# XRP_Controller.net
KiCad netlist of a schematic drawn in EAGLE
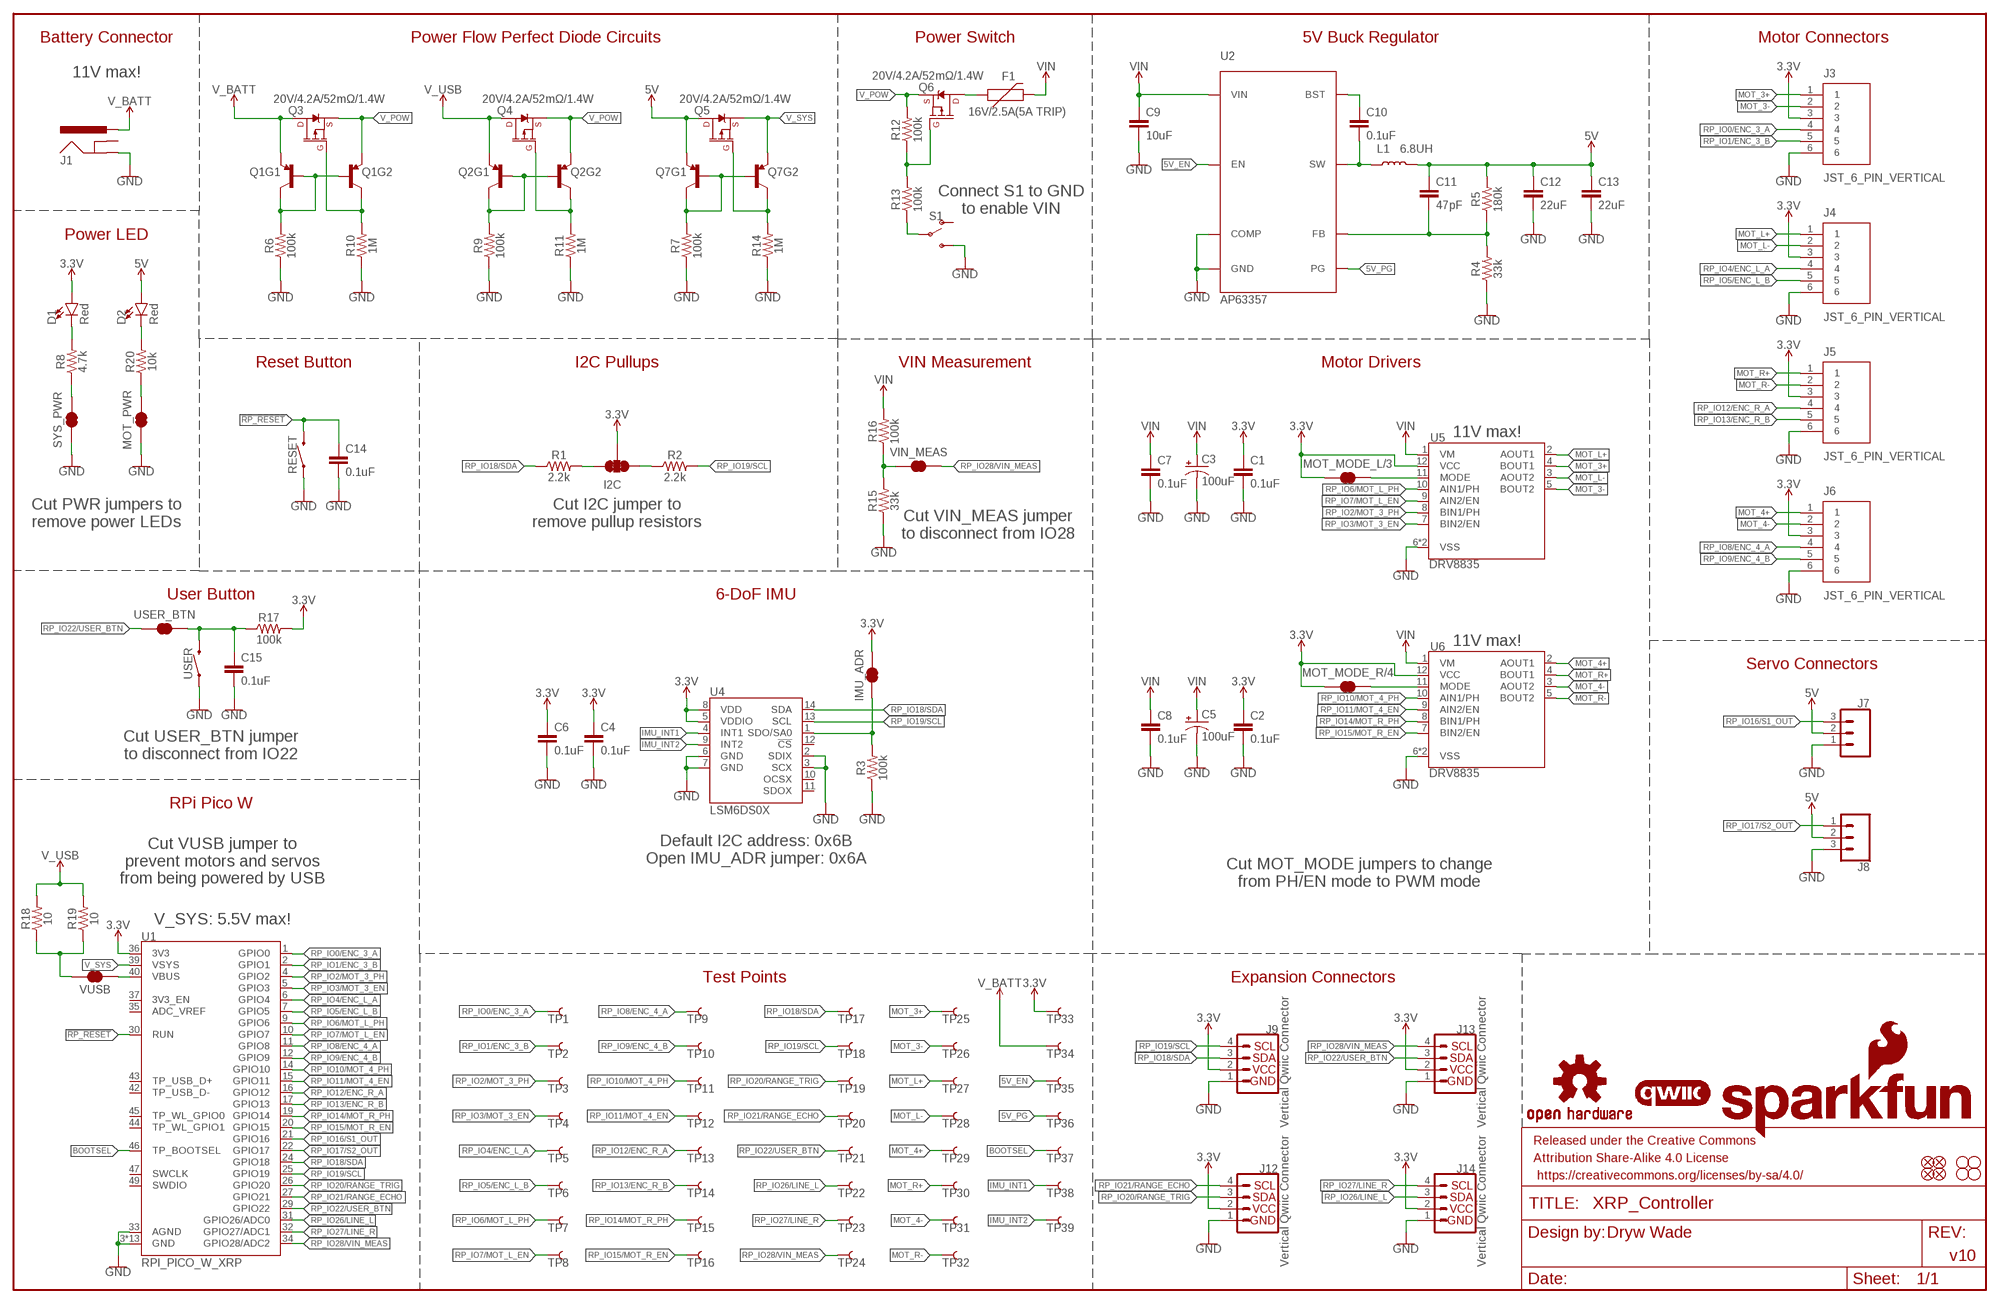
[diagram p0: schematic, sheet 1]

(export (version "E")
  (design (tool "Eeschema 10.0.6"))
  (components
    (comp (ref "C1")
      (value "0.1uF")
      (footprint "eagle-import:0603")
      (libsource (lib "eagle-import") (part "0.1UF-0603-25V-(+80/-20%)"))
    )
    (comp (ref "C2")
      (value "0.1uF")
      (footprint "eagle-import:0603")
      (libsource (lib "eagle-import") (part "0.1UF-0603-25V-(+80/-20%)"))
    )
    (comp (ref "C3")
      (value "100uF")
      (footprint "eagle-import:PANASONIC_D")
      (libsource (lib "eagle-import") (part "100UF-POLAR-25V-20%-SMD(ELEC)"))
    )
    (comp (ref "C4")
      (value "0.1uF")
      (footprint "eagle-import:0603")
      (libsource (lib "eagle-import") (part "0.1UF-0603-25V-(+80/-20%)"))
    )
    (comp (ref "C5")
      (value "100uF")
      (footprint "eagle-import:PANASONIC_D")
      (libsource (lib "eagle-import") (part "100UF-POLAR-25V-20%-SMD(ELEC)"))
    )
    (comp (ref "C6")
      (value "0.1uF")
      (footprint "eagle-import:0603")
      (libsource (lib "eagle-import") (part "0.1UF-0603-25V-(+80/-20%)"))
    )
    (comp (ref "C7")
      (value "0.1uF")
      (footprint "eagle-import:0603")
      (libsource (lib "eagle-import") (part "0.1UF-0603-25V-(+80/-20%)"))
    )
    (comp (ref "C8")
      (value "0.1uF")
      (footprint "eagle-import:0603")
      (libsource (lib "eagle-import") (part "0.1UF-0603-25V-(+80/-20%)"))
    )
    (comp (ref "C9")
      (value "10uF")
      (footprint "eagle-import:0805")
      (libsource (lib "eagle-import") (part "10UF-0805-25V-10%"))
    )
    (comp (ref "C10")
      (value "0.1uF")
      (footprint "eagle-import:0603")
      (libsource (lib "eagle-import") (part "0.1UF-0603-25V-(+80/-20%)"))
    )
    (comp (ref "C11")
      (value "47pF")
      (footprint "eagle-import:0603")
      (libsource (lib "eagle-import") (part "47PF-0603-50V-5%"))
    )
    (comp (ref "C12")
      (value "22uF")
      (footprint "eagle-import:0805")
      (libsource (lib "eagle-import") (part "22UF-0805-16V-20%"))
    )
    (comp (ref "C13")
      (value "22uF")
      (footprint "eagle-import:0805")
      (libsource (lib "eagle-import") (part "22UF-0805-16V-20%"))
    )
    (comp (ref "C14")
      (value "0.1uF")
      (footprint "eagle-import:0603")
      (libsource (lib "eagle-import") (part "0.1UF-0603-25V-(+80/-20%)"))
    )
    (comp (ref "C15")
      (value "0.1uF")
      (footprint "eagle-import:0603")
      (libsource (lib "eagle-import") (part "0.1UF-0603-25V-(+80/-20%)"))
    )
    (comp (ref "D1")
      (value "Red")
      (footprint "eagle-import:LED-0603")
      (libsource (lib "eagle-import") (part "LED-RED_0603-KB"))
    )
    (comp (ref "D2")
      (value "Red")
      (footprint "eagle-import:LED-0603")
      (libsource (lib "eagle-import") (part "LED-RED_0603-KB"))
    )
    (comp (ref "F1")
      (value "16V/2.5A(5A TRIP)")
      (footprint "eagle-import:1812")
      (libsource (lib "eagle-import") (part "PPTC_16V_2.5A"))
    )
    (comp (ref "FD1")
      (value "FIDUCIAL1X2")
      (footprint "eagle-import:FIDUCIAL-1X2")
      (libsource (lib "eagle-import") (part "FIDUCIAL1X2"))
    )
    (comp (ref "FD2")
      (value "FIDUCIAL1X2")
      (footprint "eagle-import:FIDUCIAL-1X2")
      (libsource (lib "eagle-import") (part "FIDUCIAL1X2"))
    )
    (comp (ref "FD3")
      (value "FIDUCIAL1X2")
      (footprint "eagle-import:FIDUCIAL-1X2")
      (libsource (lib "eagle-import") (part "FIDUCIAL1X2"))
    )
    (comp (ref "FD4")
      (value "FIDUCIAL1X2")
      (footprint "eagle-import:FIDUCIAL-1X2")
      (libsource (lib "eagle-import") (part "FIDUCIAL1X2"))
    )
    (comp (ref "FRAME1")
      (value "FRAME-LEDGER")
      (footprint "eagle-import:CREATIVE_COMMONS")
      (libsource (lib "eagle-import") (part "FRAME-LEDGER"))
    )
    (comp (ref "H1")
      (value "STAND-OFF")
      (footprint "eagle-import:STAND-OFF")
      (libsource (lib "eagle-import") (part "STAND-OFF"))
    )
    (comp (ref "H2")
      (value "STAND-OFF")
      (footprint "eagle-import:STAND-OFF")
      (libsource (lib "eagle-import") (part "STAND-OFF"))
    )
    (comp (ref "H3")
      (value "STAND-OFF")
      (footprint "eagle-import:STAND-OFF")
      (libsource (lib "eagle-import") (part "STAND-OFF"))
    )
    (comp (ref "H4")
      (value "STAND-OFF")
      (footprint "eagle-import:STAND-OFF")
      (libsource (lib "eagle-import") (part "STAND-OFF"))
    )
    (comp (ref "I2C")
      (value "JUMPER-SMT_3_2-NC_TRACE_SILK")
      (footprint "eagle-import:SMT-JUMPER_3_2-NC_TRACE_SILK")
      (libsource (lib "eagle-import") (part "JUMPER-SMT_3_2-NC_TRACE_SILK"))
    )
    (comp (ref "IMU_ADR")
      (value "JUMPER-SMT_2_NC_TRACE_SILK")
      (footprint "eagle-import:SMT-JUMPER_2_NC_TRACE_SILK")
      (libsource (lib "eagle-import") (part "JUMPER-SMT_2_NC_TRACE_SILK"))
    )
    (comp (ref "J1")
      (value "POWER_JACKPOWER_JACK_SLOT")
      (footprint "eagle-import:POWER_JACK_PTH_SLOT")
      (libsource (lib "eagle-import") (part "POWER_JACKPOWER_JACK_SLOT"))
    )
    (comp (ref "J3")
      (value "JST_6_PIN_VERTICAL")
      (footprint "eagle-import:JST-6-SMD-VERT-1.0MM")
      (libsource (lib "eagle-import") (part "JST_6_PIN_VERTICAL"))
    )
    (comp (ref "J4")
      (value "JST_6_PIN_VERTICAL")
      (footprint "eagle-import:JST-6-SMD-VERT-1.0MM")
      (libsource (lib "eagle-import") (part "JST_6_PIN_VERTICAL"))
    )
    (comp (ref "J5")
      (value "JST_6_PIN_VERTICAL")
      (footprint "eagle-import:JST-6-SMD-VERT-1.0MM")
      (libsource (lib "eagle-import") (part "JST_6_PIN_VERTICAL"))
    )
    (comp (ref "J6")
      (value "JST_6_PIN_VERTICAL")
      (footprint "eagle-import:JST-6-SMD-VERT-1.0MM")
      (libsource (lib "eagle-import") (part "JST_6_PIN_VERTICAL"))
    )
    (comp (ref "J7")
      (value "CONN_03LOCK_NO_SILK")
      (footprint "eagle-import:1X03_LOCK_NO_SILK")
      (libsource (lib "eagle-import") (part "CONN_03LOCK_NO_SILK"))
    )
    (comp (ref "J8")
      (value "CONN_03LOCK_NO_SILK")
      (footprint "eagle-import:1X03_LOCK_NO_SILK")
      (libsource (lib "eagle-import") (part "CONN_03LOCK_NO_SILK"))
    )
    (comp (ref "J9")
      (value "Vertical Qwiic Connector")
      (footprint "eagle-import:JST04_1MM_VERT")
      (libsource (lib "eagle-import") (part "QWIIC_CONNECTOR"))
    )
    (comp (ref "J12")
      (value "Vertical Qwiic Connector")
      (footprint "eagle-import:JST04_1MM_VERT")
      (libsource (lib "eagle-import") (part "QWIIC_CONNECTOR"))
    )
    (comp (ref "J13")
      (value "Vertical Qwiic Connector")
      (footprint "eagle-import:JST04_1MM_VERT")
      (libsource (lib "eagle-import") (part "QWIIC_CONNECTOR"))
    )
    (comp (ref "J14")
      (value "Vertical Qwiic Connector")
      (footprint "eagle-import:JST04_1MM_VERT")
      (libsource (lib "eagle-import") (part "QWIIC_CONNECTOR"))
    )
    (comp (ref "L1")
      (value "6.8UH")
      (footprint "eagle-import:07A7_6U8H")
      (libsource (lib "eagle-import") (part "6.8UH"))
    )
    (comp (ref "LOGO1")
      (value "OSHW-LOGOS")
      (footprint "eagle-import:OSHW-LOGO-S")
      (libsource (lib "eagle-import") (part "OSHW-LOGOS"))
    )
    (comp (ref "LOGO3")
      (value "SFE_LOGO_NAME_FLAME.3_INCH")
      (footprint "eagle-import:SFE_LOGO_NAME_FLAME_.3")
      (libsource (lib "eagle-import") (part "SFE_LOGO_NAME_FLAME.3_INCH"))
    )
    (comp (ref "MOT_MODE_L/3")
      (value "JUMPER-SMT_2_NC_TRACE_SILK")
      (footprint "eagle-import:SMT-JUMPER_2_NC_TRACE_SILK")
      (libsource (lib "eagle-import") (part "JUMPER-SMT_2_NC_TRACE_SILK"))
    )
    (comp (ref "MOT_MODE_R/4")
      (value "JUMPER-SMT_2_NC_TRACE_SILK")
      (footprint "eagle-import:SMT-JUMPER_2_NC_TRACE_SILK")
      (libsource (lib "eagle-import") (part "JUMPER-SMT_2_NC_TRACE_SILK"))
    )
    (comp (ref "MOT_PWR")
      (value "JUMPER-SMT_2_NC_TRACE_SILK")
      (footprint "eagle-import:SMT-JUMPER_2_NC_TRACE_SILK")
      (libsource (lib "eagle-import") (part "JUMPER-SMT_2_NC_TRACE_SILK"))
    )
    (comp (ref "Q1")
      (value "TRANS_PNP_DUALSOT-363")
      (footprint "eagle-import:SOT363_PHILIPS")
      (libsource (lib "eagle-import") (part "TRANS_PNP_DUALSOT-363"))
    )
    (comp (ref "Q2")
      (value "TRANS_PNP_DUALSOT-363")
      (footprint "eagle-import:SOT363_PHILIPS")
      (libsource (lib "eagle-import") (part "TRANS_PNP_DUALSOT-363"))
    )
    (comp (ref "Q3")
      (value "20V/4.2A/52mΩ/1.4W")
      (footprint "eagle-import:SOT23-3")
      (libsource (lib "eagle-import") (part "MOSFET_PCH-DMG2305UX-7"))
    )
    (comp (ref "Q4")
      (value "20V/4.2A/52mΩ/1.4W")
      (footprint "eagle-import:SOT23-3")
      (libsource (lib "eagle-import") (part "MOSFET_PCH-DMG2305UX-7"))
    )
    (comp (ref "Q5")
      (value "20V/4.2A/52mΩ/1.4W")
      (footprint "eagle-import:SOT23-3")
      (libsource (lib "eagle-import") (part "MOSFET_PCH-DMG2305UX-7"))
    )
    (comp (ref "Q6")
      (value "20V/4.2A/52mΩ/1.4W")
      (footprint "eagle-import:SOT23-3")
      (libsource (lib "eagle-import") (part "MOSFET_PCH-DMG2305UX-7"))
    )
    (comp (ref "Q7")
      (value "TRANS_PNP_DUALSOT-363")
      (footprint "eagle-import:SOT363_PHILIPS")
      (libsource (lib "eagle-import") (part "TRANS_PNP_DUALSOT-363"))
    )
    (comp (ref "R1")
      (value "2.2k")
      (footprint "eagle-import:0603")
      (libsource (lib "eagle-import") (part "2.2KOHM-0603-1/10W-1%"))
    )
    (comp (ref "R2")
      (value "2.2k")
      (footprint "eagle-import:0603")
      (libsource (lib "eagle-import") (part "2.2KOHM-0603-1/10W-1%"))
    )
    (comp (ref "R3")
      (value "100k")
      (footprint "eagle-import:0603")
      (libsource (lib "eagle-import") (part "100KOHM-0603-1/10W-1%"))
    )
    (comp (ref "R4")
      (value "33k")
      (footprint "eagle-import:0603")
      (libsource (lib "eagle-import") (part "33KOHM-0603-1/10W-1%"))
    )
    (comp (ref "R5")
      (value "180k")
      (footprint "eagle-import:0603")
      (libsource (lib "eagle-import") (part "180KOHM-0603-1/10W-1%"))
    )
    (comp (ref "R6")
      (value "100k")
      (footprint "eagle-import:0603")
      (libsource (lib "eagle-import") (part "100KOHM-0603-1/10W-1%"))
    )
    (comp (ref "R7")
      (value "100k")
      (footprint "eagle-import:0603")
      (libsource (lib "eagle-import") (part "100KOHM-0603-1/10W-1%"))
    )
    (comp (ref "R8")
      (value "4.7k")
      (footprint "eagle-import:0603")
      (libsource (lib "eagle-import") (part "4.7KOHM-0603-1/10W-1%"))
    )
    (comp (ref "R9")
      (value "100k")
      (footprint "eagle-import:0603")
      (libsource (lib "eagle-import") (part "100KOHM-0603-1/10W-1%"))
    )
    (comp (ref "R10")
      (value "1M")
      (footprint "eagle-import:0603")
      (libsource (lib "eagle-import") (part "1MOHM-0603-1/4W-5%"))
    )
    (comp (ref "R11")
      (value "1M")
      (footprint "eagle-import:0603")
      (libsource (lib "eagle-import") (part "1MOHM-0603-1/4W-5%"))
    )
    (comp (ref "R12")
      (value "100k")
      (footprint "eagle-import:0603")
      (libsource (lib "eagle-import") (part "100KOHM-0603-1/10W-1%"))
    )
    (comp (ref "R13")
      (value "100k")
      (footprint "eagle-import:0603")
      (libsource (lib "eagle-import") (part "100KOHM-0603-1/10W-1%"))
    )
    (comp (ref "R14")
      (value "1M")
      (footprint "eagle-import:0603")
      (libsource (lib "eagle-import") (part "1MOHM-0603-1/4W-5%"))
    )
    (comp (ref "R15")
      (value "33k")
      (footprint "eagle-import:0603")
      (libsource (lib "eagle-import") (part "33KOHM-0603-1/10W-1%"))
    )
    (comp (ref "R16")
      (value "100k")
      (footprint "eagle-import:0603")
      (libsource (lib "eagle-import") (part "100KOHM-0603-1/10W-1%"))
    )
    (comp (ref "R17")
      (value "100k")
      (footprint "eagle-import:0603")
      (libsource (lib "eagle-import") (part "100KOHM-0603-1/10W-1%"))
    )
    (comp (ref "R18")
      (value "10")
      (footprint "eagle-import:1206")
      (libsource (lib "eagle-import") (part "10OHM-1206-1/4W-1%"))
    )
    (comp (ref "R19")
      (value "10")
      (footprint "eagle-import:1206")
      (libsource (lib "eagle-import") (part "10OHM-1206-1/4W-1%"))
    )
    (comp (ref "R20")
      (value "10k")
      (footprint "eagle-import:0603")
      (libsource (lib "eagle-import") (part "10KOHM-0603-1/10W-1%"))
    )
    (comp (ref "RESET")
      (value "MOMENTARY-SWITCH-SPST-SMD-4.6X2.8MM")
      (footprint "eagle-import:TACTILE_SWITCH_SMD_4.6X2.8MM")
      (libsource (lib "eagle-import") (part "MOMENTARY-SWITCH-SPST-SMD-4.6X2.8MM"))
    )
    (comp (ref "S1")
      (value "SWITCH-SPDT-SMD-RIGHT-ANGLE")
      (footprint "eagle-import:SWITCH_SPST_SMD_A")
      (libsource (lib "eagle-import") (part "SWITCH-SPDT-SMD-RIGHT-ANGLE"))
    )
    (comp (ref "SYS_PWR")
      (value "JUMPER-SMT_2_NC_TRACE_SILK")
      (footprint "eagle-import:SMT-JUMPER_2_NC_TRACE_SILK")
      (libsource (lib "eagle-import") (part "JUMPER-SMT_2_NC_TRACE_SILK"))
    )
    (comp (ref "TP1")
      (value "TEST-POINT3X5")
      (footprint "eagle-import:PAD.03X.05")
      (libsource (lib "eagle-import") (part "TEST-POINT3X5"))
    )
    (comp (ref "TP2")
      (value "TEST-POINT3X5")
      (footprint "eagle-import:PAD.03X.05")
      (libsource (lib "eagle-import") (part "TEST-POINT3X5"))
    )
    (comp (ref "TP3")
      (value "TEST-POINT3X5")
      (footprint "eagle-import:PAD.03X.05")
      (libsource (lib "eagle-import") (part "TEST-POINT3X5"))
    )
    (comp (ref "TP4")
      (value "TEST-POINT3X5")
      (footprint "eagle-import:PAD.03X.05")
      (libsource (lib "eagle-import") (part "TEST-POINT3X5"))
    )
    (comp (ref "TP5")
      (value "TEST-POINT3X5")
      (footprint "eagle-import:PAD.03X.05")
      (libsource (lib "eagle-import") (part "TEST-POINT3X5"))
    )
    (comp (ref "TP6")
      (value "TEST-POINT3X5")
      (footprint "eagle-import:PAD.03X.05")
      (libsource (lib "eagle-import") (part "TEST-POINT3X5"))
    )
    (comp (ref "TP7")
      (value "TEST-POINT3X5")
      (footprint "eagle-import:PAD.03X.05")
      (libsource (lib "eagle-import") (part "TEST-POINT3X5"))
    )
    (comp (ref "TP8")
      (value "TEST-POINT3X5")
      (footprint "eagle-import:PAD.03X.05")
      (libsource (lib "eagle-import") (part "TEST-POINT3X5"))
    )
    (comp (ref "TP9")
      (value "TEST-POINT3X5")
      (footprint "eagle-import:PAD.03X.05")
      (libsource (lib "eagle-import") (part "TEST-POINT3X5"))
    )
    (comp (ref "TP10")
      (value "TEST-POINT3X5")
      (footprint "eagle-import:PAD.03X.05")
      (libsource (lib "eagle-import") (part "TEST-POINT3X5"))
    )
    (comp (ref "TP11")
      (value "TEST-POINT3X5")
      (footprint "eagle-import:PAD.03X.05")
      (libsource (lib "eagle-import") (part "TEST-POINT3X5"))
    )
    (comp (ref "TP12")
      (value "TEST-POINT3X5")
      (footprint "eagle-import:PAD.03X.05")
      (libsource (lib "eagle-import") (part "TEST-POINT3X5"))
    )
    (comp (ref "TP13")
      (value "TEST-POINT3X5")
      (footprint "eagle-import:PAD.03X.05")
      (libsource (lib "eagle-import") (part "TEST-POINT3X5"))
    )
    (comp (ref "TP14")
      (value "TEST-POINT3X5")
      (footprint "eagle-import:PAD.03X.05")
      (libsource (lib "eagle-import") (part "TEST-POINT3X5"))
    )
    (comp (ref "TP15")
      (value "TEST-POINT3X5")
      (footprint "eagle-import:PAD.03X.05")
      (libsource (lib "eagle-import") (part "TEST-POINT3X5"))
    )
    (comp (ref "TP16")
      (value "TEST-POINT3X5")
      (footprint "eagle-import:PAD.03X.05")
      (libsource (lib "eagle-import") (part "TEST-POINT3X5"))
    )
    (comp (ref "TP17")
      (value "TEST-POINT3X5")
      (footprint "eagle-import:PAD.03X.05")
      (libsource (lib "eagle-import") (part "TEST-POINT3X5"))
    )
    (comp (ref "TP18")
      (value "TEST-POINT3X5")
      (footprint "eagle-import:PAD.03X.05")
      (libsource (lib "eagle-import") (part "TEST-POINT3X5"))
    )
    (comp (ref "TP19")
      (value "TEST-POINT3X5")
      (footprint "eagle-import:PAD.03X.05")
      (libsource (lib "eagle-import") (part "TEST-POINT3X5"))
    )
    (comp (ref "TP20")
      (value "TEST-POINT3X5")
      (footprint "eagle-import:PAD.03X.05")
      (libsource (lib "eagle-import") (part "TEST-POINT3X5"))
    )
    (comp (ref "TP21")
      (value "TEST-POINT3X5")
      (footprint "eagle-import:PAD.03X.05")
      (libsource (lib "eagle-import") (part "TEST-POINT3X5"))
    )
    (comp (ref "TP22")
      (value "TEST-POINT3X5")
      (footprint "eagle-import:PAD.03X.05")
      (libsource (lib "eagle-import") (part "TEST-POINT3X5"))
    )
    (comp (ref "TP23")
      (value "TEST-POINT3X5")
      (footprint "eagle-import:PAD.03X.05")
      (libsource (lib "eagle-import") (part "TEST-POINT3X5"))
    )
    (comp (ref "TP24")
      (value "TEST-POINT3X5")
      (footprint "eagle-import:PAD.03X.05")
      (libsource (lib "eagle-import") (part "TEST-POINT3X5"))
    )
    (comp (ref "TP25")
      (value "TEST-POINT3X5")
      (footprint "eagle-import:PAD.03X.05")
      (libsource (lib "eagle-import") (part "TEST-POINT3X5"))
    )
    (comp (ref "TP26")
      (value "TEST-POINT3X5")
      (footprint "eagle-import:PAD.03X.05")
      (libsource (lib "eagle-import") (part "TEST-POINT3X5"))
    )
    (comp (ref "TP27")
      (value "TEST-POINT3X5")
      (footprint "eagle-import:PAD.03X.05")
      (libsource (lib "eagle-import") (part "TEST-POINT3X5"))
    )
    (comp (ref "TP28")
      (value "TEST-POINT3X5")
      (footprint "eagle-import:PAD.03X.05")
      (libsource (lib "eagle-import") (part "TEST-POINT3X5"))
    )
    (comp (ref "TP29")
      (value "TEST-POINT3X5")
      (footprint "eagle-import:PAD.03X.05")
      (libsource (lib "eagle-import") (part "TEST-POINT3X5"))
    )
    (comp (ref "TP30")
      (value "TEST-POINT3X5")
      (footprint "eagle-import:PAD.03X.05")
      (libsource (lib "eagle-import") (part "TEST-POINT3X5"))
    )
    (comp (ref "TP31")
      (value "TEST-POINT3X5")
      (footprint "eagle-import:PAD.03X.05")
      (libsource (lib "eagle-import") (part "TEST-POINT3X5"))
    )
    (comp (ref "TP32")
      (value "TEST-POINT3X5")
      (footprint "eagle-import:PAD.03X.05")
      (libsource (lib "eagle-import") (part "TEST-POINT3X5"))
    )
    (comp (ref "TP33")
      (value "TEST-POINT3X5")
      (footprint "eagle-import:PAD.03X.05")
      (libsource (lib "eagle-import") (part "TEST-POINT3X5"))
    )
    (comp (ref "TP34")
      (value "TEST-POINT3X5")
      (footprint "eagle-import:PAD.03X.05")
      (libsource (lib "eagle-import") (part "TEST-POINT3X5"))
    )
    (comp (ref "TP35")
      (value "TEST-POINT3X5")
      (footprint "eagle-import:PAD.03X.05")
      (libsource (lib "eagle-import") (part "TEST-POINT3X5"))
    )
    (comp (ref "TP36")
      (value "TEST-POINT3X5")
      (footprint "eagle-import:PAD.03X.05")
      (libsource (lib "eagle-import") (part "TEST-POINT3X5"))
    )
    (comp (ref "TP37")
      (value "TEST-POINT3X5")
      (footprint "eagle-import:PAD.03X.05")
      (libsource (lib "eagle-import") (part "TEST-POINT3X5"))
    )
    (comp (ref "TP38")
      (value "TEST-POINT3X5")
      (footprint "eagle-import:PAD.03X.05")
      (libsource (lib "eagle-import") (part "TEST-POINT3X5"))
    )
    (comp (ref "TP39")
      (value "TEST-POINT3X5")
      (footprint "eagle-import:PAD.03X.05")
      (libsource (lib "eagle-import") (part "TEST-POINT3X5"))
    )
    (comp (ref "U$98")
      (value "QWIIC_LOGO")
      (footprint "eagle-import:QWIIC_INVERTED")
      (libsource (lib "eagle-import") (part "QWIIC_LOGO"))
    )
    (comp (ref "U1")
      (value "RPI_PICO_W_XRP")
      (footprint "eagle-import:RPI_PICO_W")
      (libsource (lib "eagle-import") (part "RPI_PICO_W_XRP"))
    )
    (comp (ref "U2")
      (value "AP63357")
      (footprint "eagle-import:V-DFN3020-13")
      (libsource (lib "eagle-import") (part "AP63357"))
    )
    (comp (ref "U4")
      (value "LSM6DS0X")
      (footprint "eagle-import:LGA14L")
      (libsource (lib "eagle-import") (part "LSM6DSOX_XRP"))
    )
    (comp (ref "U5")
      (value "DRV8835")
      (footprint "eagle-import:WSON-12")
      (libsource (lib "eagle-import") (part "DRV883X"))
    )
    (comp (ref "U6")
      (value "DRV8835")
      (footprint "eagle-import:WSON-12")
      (libsource (lib "eagle-import") (part "DRV883X"))
    )
    (comp (ref "USER")
      (value "MOMENTARY-SWITCH-SPST-SMD-4.6X2.8MM")
      (footprint "eagle-import:TACTILE_SWITCH_SMD_4.6X2.8MM")
      (libsource (lib "eagle-import") (part "MOMENTARY-SWITCH-SPST-SMD-4.6X2.8MM"))
    )
    (comp (ref "USER_BTN")
      (value "JUMPER-SMT_2_NC_TRACE_SILK")
      (footprint "eagle-import:SMT-JUMPER_2_NC_TRACE_SILK")
      (libsource (lib "eagle-import") (part "JUMPER-SMT_2_NC_TRACE_SILK"))
    )
    (comp (ref "VIN_MEAS")
      (value "JUMPER-SMT_2_NC_TRACE_SILK")
      (footprint "eagle-import:SMT-JUMPER_2_NC_TRACE_SILK")
      (libsource (lib "eagle-import") (part "JUMPER-SMT_2_NC_TRACE_SILK"))
    )
    (comp (ref "VUSB")
      (value "JUMPER-SMT_2_NC_TRACE_SILK")
      (footprint "eagle-import:SMT-JUMPER_2_NC_TRACE_SILK")
      (libsource (lib "eagle-import") (part "JUMPER-SMT_2_NC_TRACE_SILK"))
    )
  )
  (nets
    (net (code "1") (name "/~{RP_RESET}") (class "Default")
      (node (ref "C14") (pin "1") (pinfunction "1_1") (pintype "passive"))
      (node (ref "RESET") (pin "3") (pinfunction "2_3") (pintype "passive"))
      (node (ref "RESET") (pin "4") (pinfunction "2_4") (pintype "passive"))
      (node (ref "U1") (pin "30") (pinfunction "RUN_30") (pintype "bidirectional"))
    )
    (net (code "2") (name "3.3V") (class "Default")
      (node (ref "C1") (pin "1") (pinfunction "1_1") (pintype "passive"))
      (node (ref "C2") (pin "1") (pinfunction "1_1") (pintype "passive"))
      (node (ref "C4") (pin "1") (pinfunction "1_1") (pintype "passive"))
      (node (ref "C6") (pin "1") (pinfunction "1_1") (pintype "passive"))
      (node (ref "D1") (pin "A") (pinfunction "A_A") (pintype "passive"))
      (node (ref "I2C") (pin "2") (pinfunction "2_2") (pintype "passive"))
      (node (ref "IMU_ADR") (pin "2") (pinfunction "2_2") (pintype "passive"))
      (node (ref "J12") (pin "2") (pinfunction "2_2") (pintype "power_in"))
      (node (ref "J13") (pin "2") (pinfunction "2_2") (pintype "power_in"))
      (node (ref "J14") (pin "2") (pinfunction "2_2") (pintype "power_in"))
      (node (ref "J3") (pin "3") (pinfunction "3_3") (pintype "bidirectional"))
      (node (ref "J4") (pin "3") (pinfunction "3_3") (pintype "bidirectional"))
      (node (ref "J5") (pin "3") (pinfunction "3_3") (pintype "bidirectional"))
      (node (ref "J6") (pin "3") (pinfunction "3_3") (pintype "bidirectional"))
      (node (ref "J9") (pin "2") (pinfunction "2_2") (pintype "power_in"))
      (node (ref "MOT_MODE_L/3") (pin "2") (pinfunction "2_2") (pintype "passive"))
      (node (ref "MOT_MODE_R/4") (pin "2") (pinfunction "2_2") (pintype "passive"))
      (node (ref "R17") (pin "2") (pinfunction "2_2") (pintype "passive"))
      (node (ref "TP33") (pin "1") (pinfunction "1_1") (pintype "bidirectional"))
      (node (ref "U1") (pin "36") (pinfunction "3V3_36") (pintype "bidirectional"))
      (node (ref "U4") (pin "5") (pinfunction "VDDIO_5") (pintype "bidirectional"))
      (node (ref "U4") (pin "8") (pinfunction "VDD_8") (pintype "bidirectional"))
      (node (ref "U5") (pin "12") (pinfunction "VCC_12") (pintype "bidirectional"))
      (node (ref "U6") (pin "12") (pinfunction "VCC_12") (pintype "bidirectional"))
    )
    (net (code "3") (name "5V") (class "Default")
      (node (ref "C11") (pin "1") (pinfunction "1_1") (pintype "passive"))
      (node (ref "C12") (pin "1") (pinfunction "1_1") (pintype "passive"))
      (node (ref "C13") (pin "1") (pinfunction "1_1") (pintype "passive"))
      (node (ref "D2") (pin "A") (pinfunction "A_A") (pintype "passive"))
      (node (ref "J7") (pin "2") (pinfunction "2_2") (pintype "passive"))
      (node (ref "J8") (pin "2") (pinfunction "2_2") (pintype "passive"))
      (node (ref "L1") (pin "P$2") (pinfunction "2_P$2") (pintype "passive"))
      (node (ref "Q5") (pin "3") (pinfunction "D_3") (pintype "bidirectional"))
      (node (ref "Q7") (pin "1") (pinfunction "E_1") (pintype "passive"))
      (node (ref "R5") (pin "2") (pinfunction "2_2") (pintype "passive"))
    )
    (net (code "4") (name "5V_EN") (class "Default")
      (node (ref "TP35") (pin "1") (pinfunction "1_1") (pintype "bidirectional"))
      (node (ref "U2") (pin "P$2") (pinfunction "EN_P$2") (pintype "bidirectional"))
    )
    (net (code "5") (name "5V_PG") (class "Default")
      (node (ref "TP36") (pin "1") (pinfunction "1_1") (pintype "bidirectional"))
      (node (ref "U2") (pin "P$5") (pinfunction "PG_P$5") (pintype "output"))
    )
    (net (code "6") (name "BOOTSEL") (class "Default")
      (node (ref "TP37") (pin "1") (pinfunction "1_1") (pintype "bidirectional"))
      (node (ref "U1") (pin "46") (pinfunction "TP_BOOTSEL_46") (pintype "bidirectional"))
    )
    (net (code "7") (name "GND") (class "Default")
      (node (ref "C1") (pin "2") (pinfunction "2_2") (pintype "passive"))
      (node (ref "C12") (pin "2") (pinfunction "2_2") (pintype "passive"))
      (node (ref "C13") (pin "2") (pinfunction "2_2") (pintype "passive"))
      (node (ref "C14") (pin "2") (pinfunction "2_2") (pintype "passive"))
      (node (ref "C15") (pin "2") (pinfunction "2_2") (pintype "passive"))
      (node (ref "C2") (pin "2") (pinfunction "2_2") (pintype "passive"))
      (node (ref "C3") (pin "-") (pinfunction "-_-") (pintype "passive"))
      (node (ref "C4") (pin "2") (pinfunction "2_2") (pintype "passive"))
      (node (ref "C5") (pin "-") (pinfunction "-_-") (pintype "passive"))
      (node (ref "C6") (pin "2") (pinfunction "2_2") (pintype "passive"))
      (node (ref "C7") (pin "2") (pinfunction "2_2") (pintype "passive"))
      (node (ref "C8") (pin "2") (pinfunction "2_2") (pintype "passive"))
      (node (ref "C9") (pin "2") (pinfunction "2_2") (pintype "passive"))
      (node (ref "J1") (pin "GND") (pinfunction "GND_GND") (pintype "bidirectional"))
      (node (ref "J12") (pin "1") (pinfunction "1_1") (pintype "power_in"))
      (node (ref "J13") (pin "1") (pinfunction "1_1") (pintype "power_in"))
      (node (ref "J14") (pin "1") (pinfunction "1_1") (pintype "power_in"))
      (node (ref "J3") (pin "6") (pinfunction "6_6") (pintype "bidirectional"))
      (node (ref "J4") (pin "6") (pinfunction "6_6") (pintype "bidirectional"))
      (node (ref "J5") (pin "6") (pinfunction "6_6") (pintype "bidirectional"))
      (node (ref "J6") (pin "6") (pinfunction "6_6") (pintype "bidirectional"))
      (node (ref "J7") (pin "1") (pinfunction "1_1") (pintype "passive"))
      (node (ref "J8") (pin "3") (pinfunction "3_3") (pintype "passive"))
      (node (ref "J9") (pin "1") (pinfunction "1_1") (pintype "power_in"))
      (node (ref "MOT_PWR") (pin "1") (pinfunction "1_1") (pintype "passive"))
      (node (ref "R10") (pin "1") (pinfunction "1_1") (pintype "passive"))
      (node (ref "R11") (pin "1") (pinfunction "1_1") (pintype "passive"))
      (node (ref "R14") (pin "1") (pinfunction "1_1") (pintype "passive"))
      (node (ref "R15") (pin "1") (pinfunction "1_1") (pintype "passive"))
      (node (ref "R3") (pin "1") (pinfunction "1_1") (pintype "passive"))
      (node (ref "R4") (pin "1") (pinfunction "1_1") (pintype "passive"))
      (node (ref "R6") (pin "1") (pinfunction "1_1") (pintype "passive"))
      (node (ref "R7") (pin "1") (pinfunction "1_1") (pintype "passive"))
      (node (ref "R9") (pin "1") (pinfunction "1_1") (pintype "passive"))
      (node (ref "RESET") (pin "1") (pinfunction "1_1") (pintype "passive"))
      (node (ref "RESET") (pin "2") (pinfunction "1_2") (pintype "passive"))
      (node (ref "S1") (pin "3") (pinfunction "S_3") (pintype "passive"))
      (node (ref "SYS_PWR") (pin "1") (pinfunction "1_1") (pintype "passive"))
      (node (ref "U1") (pin "13") (pinfunction "GND_13") (pintype "bidirectional"))
      (node (ref "U1") (pin "18") (pinfunction "GND_18") (pintype "bidirectional"))
      (node (ref "U1") (pin "23") (pinfunction "GND_23") (pintype "bidirectional"))
      (node (ref "U1") (pin "28") (pinfunction "GND_28") (pintype "bidirectional"))
      (node (ref "U1") (pin "3") (pinfunction "GND_3") (pintype "bidirectional"))
      (node (ref "U1") (pin "33") (pinfunction "AGND_33") (pintype "bidirectional"))
      (node (ref "U1") (pin "38") (pinfunction "GND_38") (pintype "bidirectional"))
      (node (ref "U1") (pin "41") (pinfunction "GND_41") (pintype "bidirectional"))
      (node (ref "U1") (pin "48") (pinfunction "GND_48") (pintype "bidirectional"))
      (node (ref "U1") (pin "8") (pinfunction "GND_8") (pintype "bidirectional"))
      (node (ref "U1") (pin "A") (pinfunction "GND_A") (pintype "bidirectional"))
      (node (ref "U1") (pin "B") (pinfunction "GND_B") (pintype "bidirectional"))
      (node (ref "U1") (pin "C") (pinfunction "GND_C") (pintype "bidirectional"))
      (node (ref "U1") (pin "D") (pinfunction "GND_D") (pintype "bidirectional"))
      (node (ref "U2") (pin "P$4") (pinfunction "COMP_P$4") (pintype "bidirectional"))
      (node (ref "U2") (pin "P$8") (pinfunction "GND_P$8") (pintype "power_in"))
      (node (ref "U4") (pin "2") (pinfunction "SDIX_2") (pintype "bidirectional"))
      (node (ref "U4") (pin "3") (pinfunction "SCX_3") (pintype "bidirectional"))
      (node (ref "U4") (pin "6") (pinfunction "GND_6") (pintype "bidirectional"))
      (node (ref "U4") (pin "7") (pinfunction "GND_7") (pintype "bidirectional"))
      (node (ref "U5") (pin "6") (pinfunction "VSS_6") (pintype "bidirectional"))
      (node (ref "U5") (pin "PAD") (pinfunction "VSS_PAD") (pintype "bidirectional"))
      (node (ref "U6") (pin "6") (pinfunction "VSS_6") (pintype "bidirectional"))
      (node (ref "U6") (pin "PAD") (pinfunction "VSS_PAD") (pintype "bidirectional"))
      (node (ref "USER") (pin "1") (pinfunction "1_1") (pintype "passive"))
      (node (ref "USER") (pin "2") (pinfunction "1_2") (pintype "passive"))
    )
    (net (code "8") (name "IMU_INT1") (class "Default")
      (node (ref "TP38") (pin "1") (pinfunction "1_1") (pintype "bidirectional"))
      (node (ref "U4") (pin "4") (pinfunction "INT1_4") (pintype "bidirectional"))
    )
    (net (code "9") (name "IMU_INT2") (class "Default")
      (node (ref "TP39") (pin "1") (pinfunction "1_1") (pintype "bidirectional"))
      (node (ref "U4") (pin "9") (pinfunction "INT2_9") (pintype "bidirectional"))
    )
    (net (code "10") (name "MOT_3+") (class "Default")
      (node (ref "J3") (pin "1") (pinfunction "1_1") (pintype "bidirectional"))
      (node (ref "TP25") (pin "1") (pinfunction "1_1") (pintype "bidirectional"))
      (node (ref "U5") (pin "4") (pinfunction "BOUT1_4") (pintype "bidirectional"))
    )
    (net (code "11") (name "MOT_3-") (class "Default")
      (node (ref "J3") (pin "2") (pinfunction "2_2") (pintype "bidirectional"))
      (node (ref "TP26") (pin "1") (pinfunction "1_1") (pintype "bidirectional"))
      (node (ref "U5") (pin "5") (pinfunction "BOUT2_5") (pintype "bidirectional"))
    )
    (net (code "12") (name "MOT_4+") (class "Default")
      (node (ref "J6") (pin "1") (pinfunction "1_1") (pintype "bidirectional"))
      (node (ref "TP29") (pin "1") (pinfunction "1_1") (pintype "bidirectional"))
      (node (ref "U6") (pin "2") (pinfunction "AOUT1_2") (pintype "bidirectional"))
    )
    (net (code "13") (name "MOT_4-") (class "Default")
      (node (ref "J6") (pin "2") (pinfunction "2_2") (pintype "bidirectional"))
      (node (ref "TP31") (pin "1") (pinfunction "1_1") (pintype "bidirectional"))
      (node (ref "U6") (pin "3") (pinfunction "AOUT2_3") (pintype "bidirectional"))
    )
    (net (code "14") (name "MOT_L+") (class "Default")
      (node (ref "J4") (pin "1") (pinfunction "1_1") (pintype "bidirectional"))
      (node (ref "TP27") (pin "1") (pinfunction "1_1") (pintype "bidirectional"))
      (node (ref "U5") (pin "2") (pinfunction "AOUT1_2") (pintype "bidirectional"))
    )
    (net (code "15") (name "MOT_L-") (class "Default")
      (node (ref "J4") (pin "2") (pinfunction "2_2") (pintype "bidirectional"))
      (node (ref "TP28") (pin "1") (pinfunction "1_1") (pintype "bidirectional"))
      (node (ref "U5") (pin "3") (pinfunction "AOUT2_3") (pintype "bidirectional"))
    )
    (net (code "16") (name "MOT_R+") (class "Default")
      (node (ref "J5") (pin "1") (pinfunction "1_1") (pintype "bidirectional"))
      (node (ref "TP30") (pin "1") (pinfunction "1_1") (pintype "bidirectional"))
      (node (ref "U6") (pin "4") (pinfunction "BOUT1_4") (pintype "bidirectional"))
    )
    (net (code "17") (name "MOT_R-") (class "Default")
      (node (ref "J5") (pin "2") (pinfunction "2_2") (pintype "bidirectional"))
      (node (ref "TP32") (pin "1") (pinfunction "1_1") (pintype "bidirectional"))
      (node (ref "U6") (pin "5") (pinfunction "BOUT2_5") (pintype "bidirectional"))
    )
    (net (code "18") (name "Net-(C15-Pad1)") (class "Default")
      (node (ref "C15") (pin "1") (pinfunction "1_1") (pintype "passive"))
      (node (ref "R17") (pin "1") (pinfunction "1_1") (pintype "passive"))
      (node (ref "USER") (pin "3") (pinfunction "2_3") (pintype "passive"))
      (node (ref "USER") (pin "4") (pinfunction "2_4") (pintype "passive"))
      (node (ref "USER_BTN") (pin "1") (pinfunction "1_1") (pintype "passive"))
    )
    (net (code "19") (name "Net-(D1-PadC)") (class "Default")
      (node (ref "D1") (pin "C") (pinfunction "C_C") (pintype "passive"))
      (node (ref "R8") (pin "2") (pinfunction "2_2") (pintype "passive"))
    )
    (net (code "20") (name "Net-(D2-PadC)") (class "Default")
      (node (ref "D2") (pin "C") (pinfunction "C_C") (pintype "passive"))
      (node (ref "R20") (pin "2") (pinfunction "2_2") (pintype "passive"))
    )
    (net (code "21") (name "Net-(I2C-Pad1)") (class "Default")
      (node (ref "I2C") (pin "1") (pinfunction "1_1") (pintype "passive"))
      (node (ref "R2") (pin "1") (pinfunction "1_1") (pintype "passive"))
    )
    (net (code "22") (name "Net-(I2C-Pad3)") (class "Default")
      (node (ref "I2C") (pin "3") (pinfunction "3_3") (pintype "passive"))
      (node (ref "R1") (pin "2") (pinfunction "2_2") (pintype "passive"))
    )
    (net (code "23") (name "Net-(L1-1)") (class "Default")
      (node (ref "C10") (pin "2") (pinfunction "2_2") (pintype "passive"))
      (node (ref "L1") (pin "P$1") (pinfunction "1_P$1") (pintype "passive"))
      (node (ref "U2") (pin "P$7") (pinfunction "SW_P$7") (pintype "power_in"))
      (node (ref "U2") (pin "P$9") (pinfunction "SW_P$9") (pintype "power_in"))
    )
    (net (code "24") (name "Net-(MOT_PWR-Pad2)") (class "Default")
      (node (ref "MOT_PWR") (pin "2") (pinfunction "2_2") (pintype "passive"))
      (node (ref "R20") (pin "1") (pinfunction "1_1") (pintype "passive"))
    )
    (net (code "25") (name "Net-(Q1A-B)") (class "Default")
      (node (ref "Q1") (pin "2") (pinfunction "B_2") (pintype "passive"))
      (node (ref "Q1") (pin "5") (pinfunction "B_5") (pintype "passive"))
      (node (ref "Q1") (pin "6") (pinfunction "C_6") (pintype "passive"))
      (node (ref "R6") (pin "2") (pinfunction "2_2") (pintype "passive"))
    )
    (net (code "26") (name "Net-(Q1B-C)") (class "Default")
      (node (ref "Q1") (pin "3") (pinfunction "C_3") (pintype "passive"))
      (node (ref "Q3") (pin "1") (pinfunction "G_1") (pintype "bidirectional"))
      (node (ref "R10") (pin "2") (pinfunction "2_2") (pintype "passive"))
    )
    (net (code "27") (name "Net-(Q2A-B)") (class "Default")
      (node (ref "Q2") (pin "2") (pinfunction "B_2") (pintype "passive"))
      (node (ref "Q2") (pin "5") (pinfunction "B_5") (pintype "passive"))
      (node (ref "Q2") (pin "6") (pinfunction "C_6") (pintype "passive"))
      (node (ref "R9") (pin "2") (pinfunction "2_2") (pintype "passive"))
    )
    (net (code "28") (name "Net-(Q2B-C)") (class "Default")
      (node (ref "Q2") (pin "3") (pinfunction "C_3") (pintype "passive"))
      (node (ref "Q4") (pin "1") (pinfunction "G_1") (pintype "bidirectional"))
      (node (ref "R11") (pin "2") (pinfunction "2_2") (pintype "passive"))
    )
    (net (code "29") (name "Net-(Q5-G)") (class "Default")
      (node (ref "Q5") (pin "1") (pinfunction "G_1") (pintype "bidirectional"))
      (node (ref "Q7") (pin "3") (pinfunction "C_3") (pintype "passive"))
      (node (ref "R14") (pin "2") (pinfunction "2_2") (pintype "passive"))
    )
    (net (code "30") (name "Net-(Q6-D)") (class "Default")
      (node (ref "F1") (pin "1") (pinfunction "1_1") (pintype "bidirectional"))
      (node (ref "Q6") (pin "3") (pinfunction "D_3") (pintype "bidirectional"))
    )
    (net (code "31") (name "Net-(Q6-G)") (class "Default")
      (node (ref "Q6") (pin "1") (pinfunction "G_1") (pintype "bidirectional"))
      (node (ref "R12") (pin "1") (pinfunction "1_1") (pintype "passive"))
      (node (ref "R13") (pin "2") (pinfunction "2_2") (pintype "passive"))
    )
    (net (code "32") (name "Net-(Q7A-B)") (class "Default")
      (node (ref "Q7") (pin "2") (pinfunction "B_2") (pintype "passive"))
      (node (ref "Q7") (pin "5") (pinfunction "B_5") (pintype "passive"))
      (node (ref "Q7") (pin "6") (pinfunction "C_6") (pintype "passive"))
      (node (ref "R7") (pin "2") (pinfunction "2_2") (pintype "passive"))
    )
    (net (code "33") (name "Net-(R8-Pad1)") (class "Default")
      (node (ref "R8") (pin "1") (pinfunction "1_1") (pintype "passive"))
      (node (ref "SYS_PWR") (pin "2") (pinfunction "2_2") (pintype "passive"))
    )
    (net (code "34") (name "Net-(R15-Pad2)") (class "Default")
      (node (ref "R15") (pin "2") (pinfunction "2_2") (pintype "passive"))
      (node (ref "R16") (pin "1") (pinfunction "1_1") (pintype "passive"))
      (node (ref "VIN_MEAS") (pin "2") (pinfunction "2_2") (pintype "passive"))
    )
    (net (code "35") (name "Net-(R18-Pad1)") (class "Default")
      (node (ref "R18") (pin "1") (pinfunction "1_1") (pintype "passive"))
      (node (ref "R19") (pin "1") (pinfunction "1_1") (pintype "passive"))
      (node (ref "VUSB") (pin "1") (pinfunction "1_1") (pintype "passive"))
    )
    (net (code "36") (name "Net-(S1-P)") (class "Default")
      (node (ref "R13") (pin "1") (pinfunction "1_1") (pintype "passive"))
      (node (ref "S1") (pin "2") (pinfunction "P_2") (pintype "passive"))
    )
    (net (code "37") (name "Net-(U1-VBUS)") (class "Default")
      (node (ref "U1") (pin "40") (pinfunction "VBUS_40") (pintype "bidirectional"))
      (node (ref "VUSB") (pin "2") (pinfunction "2_2") (pintype "passive"))
    )
    (net (code "38") (name "Net-(U2-BST)") (class "Default")
      (node (ref "C10") (pin "1") (pinfunction "1_1") (pintype "passive"))
      (node (ref "U2") (pin "P$6") (pinfunction "BST_P$6") (pintype "bidirectional"))
    )
    (net (code "39") (name "Net-(U2-FB)") (class "Default")
      (node (ref "C11") (pin "2") (pinfunction "2_2") (pintype "passive"))
      (node (ref "R4") (pin "2") (pinfunction "2_2") (pintype "passive"))
      (node (ref "R5") (pin "1") (pinfunction "1_1") (pintype "passive"))
      (node (ref "U2") (pin "P$3") (pinfunction "FB_P$3") (pintype "input"))
    )
    (net (code "40") (name "Net-(U4-SDO{slash}SA0)") (class "Default")
      (node (ref "IMU_ADR") (pin "1") (pinfunction "1_1") (pintype "passive"))
      (node (ref "R3") (pin "2") (pinfunction "2_2") (pintype "passive"))
      (node (ref "U4") (pin "1") (pinfunction "SDO/SA0_1") (pintype "bidirectional"))
    )
    (net (code "41") (name "Net-(U5-MODE)") (class "Default")
      (node (ref "MOT_MODE_L/3") (pin "1") (pinfunction "1_1") (pintype "passive"))
      (node (ref "U5") (pin "11") (pinfunction "MODE_11") (pintype "bidirectional"))
    )
    (net (code "42") (name "Net-(U6-MODE)") (class "Default")
      (node (ref "MOT_MODE_R/4") (pin "1") (pinfunction "1_1") (pintype "passive"))
      (node (ref "U6") (pin "11") (pinfunction "MODE_11") (pintype "bidirectional"))
    )
    (net (code "43") (name "RP_IO0{slash}ENC_3_A") (class "Default")
      (node (ref "J3") (pin "4") (pinfunction "4_4") (pintype "bidirectional"))
      (node (ref "TP1") (pin "1") (pinfunction "1_1") (pintype "bidirectional"))
      (node (ref "U1") (pin "1") (pinfunction "GPIO0_1") (pintype "bidirectional"))
    )
    (net (code "44") (name "RP_IO1{slash}ENC_3_B") (class "Default")
      (node (ref "J3") (pin "5") (pinfunction "5_5") (pintype "bidirectional"))
      (node (ref "TP2") (pin "1") (pinfunction "1_1") (pintype "bidirectional"))
      (node (ref "U1") (pin "2") (pinfunction "GPIO1_2") (pintype "bidirectional"))
    )
    (net (code "45") (name "RP_IO2{slash}MOT_3_PH") (class "Default")
      (node (ref "TP3") (pin "1") (pinfunction "1_1") (pintype "bidirectional"))
      (node (ref "U1") (pin "4") (pinfunction "GPIO2_4") (pintype "bidirectional"))
      (node (ref "U5") (pin "8") (pinfunction "BIN1/PH_8") (pintype "bidirectional"))
    )
    (net (code "46") (name "RP_IO3{slash}MOT_3_EN") (class "Default")
      (node (ref "TP4") (pin "1") (pinfunction "1_1") (pintype "bidirectional"))
      (node (ref "U1") (pin "5") (pinfunction "GPIO3_5") (pintype "bidirectional"))
      (node (ref "U5") (pin "7") (pinfunction "BIN2/EN_7") (pintype "bidirectional"))
    )
    (net (code "47") (name "RP_IO4{slash}ENC_L_A") (class "Default")
      (node (ref "J4") (pin "4") (pinfunction "4_4") (pintype "bidirectional"))
      (node (ref "TP5") (pin "1") (pinfunction "1_1") (pintype "bidirectional"))
      (node (ref "U1") (pin "6") (pinfunction "GPIO4_6") (pintype "bidirectional"))
    )
    (net (code "48") (name "RP_IO5{slash}ENC_L_B") (class "Default")
      (node (ref "J4") (pin "5") (pinfunction "5_5") (pintype "bidirectional"))
      (node (ref "TP6") (pin "1") (pinfunction "1_1") (pintype "bidirectional"))
      (node (ref "U1") (pin "7") (pinfunction "GPIO5_7") (pintype "bidirectional"))
    )
    (net (code "49") (name "RP_IO6{slash}MOT_L_PH") (class "Default")
      (node (ref "TP7") (pin "1") (pinfunction "1_1") (pintype "bidirectional"))
      (node (ref "U1") (pin "9") (pinfunction "GPIO6_9") (pintype "bidirectional"))
      (node (ref "U5") (pin "10") (pinfunction "AIN1/PH_10") (pintype "bidirectional"))
    )
    (net (code "50") (name "RP_IO7{slash}MOT_L_EN") (class "Default")
      (node (ref "TP8") (pin "1") (pinfunction "1_1") (pintype "bidirectional"))
      (node (ref "U1") (pin "10") (pinfunction "GPIO7_10") (pintype "bidirectional"))
      (node (ref "U5") (pin "9") (pinfunction "AIN2/EN_9") (pintype "bidirectional"))
    )
    (net (code "51") (name "RP_IO8{slash}ENC_4_A") (class "Default")
      (node (ref "J6") (pin "4") (pinfunction "4_4") (pintype "bidirectional"))
      (node (ref "TP9") (pin "1") (pinfunction "1_1") (pintype "bidirectional"))
      (node (ref "U1") (pin "11") (pinfunction "GPIO8_11") (pintype "bidirectional"))
    )
    (net (code "52") (name "RP_IO9{slash}ENC_4_B") (class "Default")
      (node (ref "J6") (pin "5") (pinfunction "5_5") (pintype "bidirectional"))
      (node (ref "TP10") (pin "1") (pinfunction "1_1") (pintype "bidirectional"))
      (node (ref "U1") (pin "12") (pinfunction "GPIO9_12") (pintype "bidirectional"))
    )
    (net (code "53") (name "RP_IO10{slash}MOT_4_PH") (class "Default")
      (node (ref "TP11") (pin "1") (pinfunction "1_1") (pintype "bidirectional"))
      (node (ref "U1") (pin "14") (pinfunction "GPIO10_14") (pintype "bidirectional"))
      (node (ref "U6") (pin "10") (pinfunction "AIN1/PH_10") (pintype "bidirectional"))
    )
    (net (code "54") (name "RP_IO11{slash}MOT_4_EN") (class "Default")
      (node (ref "TP12") (pin "1") (pinfunction "1_1") (pintype "bidirectional"))
      (node (ref "U1") (pin "15") (pinfunction "GPIO11_15") (pintype "bidirectional"))
      (node (ref "U6") (pin "9") (pinfunction "AIN2/EN_9") (pintype "bidirectional"))
    )
    (net (code "55") (name "RP_IO12{slash}ENC_R_A") (class "Default")
      (node (ref "J5") (pin "4") (pinfunction "4_4") (pintype "bidirectional"))
      (node (ref "TP13") (pin "1") (pinfunction "1_1") (pintype "bidirectional"))
      (node (ref "U1") (pin "16") (pinfunction "GPIO12_16") (pintype "bidirectional"))
    )
    (net (code "56") (name "RP_IO13{slash}ENC_R_B") (class "Default")
      (node (ref "J5") (pin "5") (pinfunction "5_5") (pintype "bidirectional"))
      (node (ref "TP14") (pin "1") (pinfunction "1_1") (pintype "bidirectional"))
      (node (ref "U1") (pin "17") (pinfunction "GPIO13_17") (pintype "bidirectional"))
    )
    (net (code "57") (name "RP_IO14{slash}MOT_R_PH") (class "Default")
      (node (ref "TP15") (pin "1") (pinfunction "1_1") (pintype "bidirectional"))
      (node (ref "U1") (pin "19") (pinfunction "GPIO14_19") (pintype "bidirectional"))
      (node (ref "U6") (pin "8") (pinfunction "BIN1/PH_8") (pintype "bidirectional"))
    )
    (net (code "58") (name "RP_IO15{slash}MOT_R_EN") (class "Default")
      (node (ref "TP16") (pin "1") (pinfunction "1_1") (pintype "bidirectional"))
      (node (ref "U1") (pin "20") (pinfunction "GPIO15_20") (pintype "bidirectional"))
      (node (ref "U6") (pin "7") (pinfunction "BIN2/EN_7") (pintype "bidirectional"))
    )
    (net (code "59") (name "RP_IO16{slash}S1_OUT") (class "Default")
      (node (ref "J7") (pin "3") (pinfunction "3_3") (pintype "passive"))
      (node (ref "U1") (pin "21") (pinfunction "GPIO16_21") (pintype "bidirectional"))
    )
    (net (code "60") (name "RP_IO17{slash}S2_OUT") (class "Default")
      (node (ref "J8") (pin "1") (pinfunction "1_1") (pintype "passive"))
      (node (ref "U1") (pin "22") (pinfunction "GPIO17_22") (pintype "bidirectional"))
    )
    (net (code "61") (name "RP_IO18{slash}SDA") (class "Default")
      (node (ref "J9") (pin "3") (pinfunction "3_3") (pintype "passive"))
      (node (ref "R1") (pin "1") (pinfunction "1_1") (pintype "passive"))
      (node (ref "TP17") (pin "1") (pinfunction "1_1") (pintype "bidirectional"))
      (node (ref "U1") (pin "24") (pinfunction "GPIO18_24") (pintype "bidirectional"))
      (node (ref "U4") (pin "14") (pinfunction "SDA_14") (pintype "bidirectional"))
    )
    (net (code "62") (name "RP_IO19{slash}SCL") (class "Default")
      (node (ref "J9") (pin "4") (pinfunction "4_4") (pintype "passive"))
      (node (ref "R2") (pin "2") (pinfunction "2_2") (pintype "passive"))
      (node (ref "TP18") (pin "1") (pinfunction "1_1") (pintype "bidirectional"))
      (node (ref "U1") (pin "25") (pinfunction "GPIO19_25") (pintype "bidirectional"))
      (node (ref "U4") (pin "13") (pinfunction "SCL_13") (pintype "bidirectional"))
    )
    (net (code "63") (name "RP_IO20{slash}RANGE_TRIG") (class "Default")
      (node (ref "J12") (pin "3") (pinfunction "3_3") (pintype "passive"))
      (node (ref "TP19") (pin "1") (pinfunction "1_1") (pintype "bidirectional"))
      (node (ref "U1") (pin "26") (pinfunction "GPIO20_26") (pintype "bidirectional"))
    )
    (net (code "64") (name "RP_IO21{slash}RANGE_ECHO") (class "Default")
      (node (ref "J12") (pin "4") (pinfunction "4_4") (pintype "passive"))
      (node (ref "TP20") (pin "1") (pinfunction "1_1") (pintype "bidirectional"))
      (node (ref "U1") (pin "27") (pinfunction "GPIO21_27") (pintype "bidirectional"))
    )
    (net (code "65") (name "RP_IO22{slash}USER_BTN") (class "Default")
      (node (ref "J13") (pin "3") (pinfunction "3_3") (pintype "passive"))
      (node (ref "TP21") (pin "1") (pinfunction "1_1") (pintype "bidirectional"))
      (node (ref "U1") (pin "29") (pinfunction "GPIO22_29") (pintype "bidirectional"))
      (node (ref "USER_BTN") (pin "2") (pinfunction "2_2") (pintype "passive"))
    )
    (net (code "66") (name "RP_IO26{slash}LINE_L") (class "Default")
      (node (ref "J14") (pin "3") (pinfunction "3_3") (pintype "passive"))
      (node (ref "TP22") (pin "1") (pinfunction "1_1") (pintype "bidirectional"))
      (node (ref "U1") (pin "31") (pinfunction "GPIO26/ADC0_31") (pintype "bidirectional"))
    )
    (net (code "67") (name "RP_IO27{slash}LINE_R") (class "Default")
      (node (ref "J14") (pin "4") (pinfunction "4_4") (pintype "passive"))
      (node (ref "TP23") (pin "1") (pinfunction "1_1") (pintype "bidirectional"))
      (node (ref "U1") (pin "32") (pinfunction "GPIO27/ADC1_32") (pintype "bidirectional"))
    )
    (net (code "68") (name "RP_IO28{slash}VIN_MEAS") (class "Default")
      (node (ref "J13") (pin "4") (pinfunction "4_4") (pintype "passive"))
      (node (ref "TP24") (pin "1") (pinfunction "1_1") (pintype "bidirectional"))
      (node (ref "U1") (pin "34") (pinfunction "GPIO28/ADC2_34") (pintype "bidirectional"))
      (node (ref "VIN_MEAS") (pin "1") (pinfunction "1_1") (pintype "passive"))
    )
    (net (code "69") (name "VIN") (class "Default")
      (node (ref "C3") (pin "+") (pinfunction "+_+") (pintype "passive"))
      (node (ref "C5") (pin "+") (pinfunction "+_+") (pintype "passive"))
      (node (ref "C7") (pin "1") (pinfunction "1_1") (pintype "passive"))
      (node (ref "C8") (pin "1") (pinfunction "1_1") (pintype "passive"))
      (node (ref "C9") (pin "1") (pinfunction "1_1") (pintype "passive"))
      (node (ref "F1") (pin "2") (pinfunction "2_2") (pintype "bidirectional"))
      (node (ref "R16") (pin "2") (pinfunction "2_2") (pintype "passive"))
      (node (ref "U2") (pin "P$1") (pinfunction "VIN_P$1") (pintype "power_in"))
      (node (ref "U5") (pin "1") (pinfunction "VM_1") (pintype "bidirectional"))
      (node (ref "U6") (pin "1") (pinfunction "VM_1") (pintype "bidirectional"))
    )
    (net (code "70") (name "V_BATT") (class "Default")
      (node (ref "J1") (pin "PWR") (pinfunction "PWR_PWR") (pintype "bidirectional"))
      (node (ref "Q1") (pin "1") (pinfunction "E_1") (pintype "passive"))
      (node (ref "Q3") (pin "3") (pinfunction "D_3") (pintype "bidirectional"))
      (node (ref "TP34") (pin "1") (pinfunction "1_1") (pintype "bidirectional"))
    )
    (net (code "71") (name "V_POW") (class "Default")
      (node (ref "Q1") (pin "4") (pinfunction "E_4") (pintype "passive"))
      (node (ref "Q2") (pin "4") (pinfunction "E_4") (pintype "passive"))
      (node (ref "Q3") (pin "2") (pinfunction "S_2") (pintype "bidirectional"))
      (node (ref "Q4") (pin "2") (pinfunction "S_2") (pintype "bidirectional"))
      (node (ref "Q6") (pin "2") (pinfunction "S_2") (pintype "bidirectional"))
      (node (ref "R12") (pin "2") (pinfunction "2_2") (pintype "passive"))
    )
    (net (code "72") (name "V_SYS") (class "Default")
      (node (ref "Q5") (pin "2") (pinfunction "S_2") (pintype "bidirectional"))
      (node (ref "Q7") (pin "4") (pinfunction "E_4") (pintype "passive"))
      (node (ref "U1") (pin "39") (pinfunction "VSYS_39") (pintype "bidirectional"))
    )
    (net (code "73") (name "V_USB") (class "Default")
      (node (ref "Q2") (pin "1") (pinfunction "E_1") (pintype "passive"))
      (node (ref "Q4") (pin "3") (pinfunction "D_3") (pintype "bidirectional"))
      (node (ref "R18") (pin "2") (pinfunction "2_2") (pintype "passive"))
      (node (ref "R19") (pin "2") (pinfunction "2_2") (pintype "passive"))
    )
    (net (code "74") (name "unconnected-(J1-PadGNDBREAK)") (class "Default")
      (node (ref "J1") (pin "GNDBREAK") (pinfunction "GNDBREAK_GNDBREAK") (pintype "bidirectional"))
    )
    (net (code "75") (name "unconnected-(S1-O-Pad1)") (class "Default")
      (node (ref "S1") (pin "1") (pinfunction "O_1") (pintype "passive"))
    )
    (net (code "76") (name "unconnected-(U1-3V3_EN-Pad37)") (class "Default")
      (node (ref "U1") (pin "37") (pinfunction "3V3_EN_37") (pintype "bidirectional"))
    )
    (net (code "77") (name "unconnected-(U1-ADC_VREF-Pad35)") (class "Default")
      (node (ref "U1") (pin "35") (pinfunction "ADC_VREF_35") (pintype "bidirectional"))
    )
    (net (code "78") (name "unconnected-(U1-SWCLK-Pad47)") (class "Default")
      (node (ref "U1") (pin "47") (pinfunction "SWCLK_47") (pintype "bidirectional"))
    )
    (net (code "79") (name "unconnected-(U1-SWDIO-Pad49)") (class "Default")
      (node (ref "U1") (pin "49") (pinfunction "SWDIO_49") (pintype "bidirectional"))
    )
    (net (code "80") (name "unconnected-(U1-TP_USB_D+-Pad43)") (class "Default")
      (node (ref "U1") (pin "43") (pinfunction "TP_USB_D+_43") (pintype "bidirectional"))
    )
    (net (code "81") (name "unconnected-(U1-TP_USB_D--Pad42)") (class "Default")
      (node (ref "U1") (pin "42") (pinfunction "TP_USB_D-_42") (pintype "bidirectional"))
    )
    (net (code "82") (name "unconnected-(U1-TP_WL_GPIO0-Pad45)") (class "Default")
      (node (ref "U1") (pin "45") (pinfunction "TP_WL_GPIO0_45") (pintype "bidirectional"))
    )
    (net (code "83") (name "unconnected-(U1-TP_WL_GPIO1-Pad44)") (class "Default")
      (node (ref "U1") (pin "44") (pinfunction "TP_WL_GPIO1_44") (pintype "bidirectional"))
    )
    (net (code "84") (name "unconnected-(U4-OCSX-Pad10)") (class "Default")
      (node (ref "U4") (pin "10") (pinfunction "OCSX_10") (pintype "bidirectional"))
    )
    (net (code "85") (name "unconnected-(U4-SDOX-Pad11)") (class "Default")
      (node (ref "U4") (pin "11") (pinfunction "SDOX_11") (pintype "bidirectional"))
    )
    (net (code "86") (name "unconnected-(U4-~{CS}-Pad12)") (class "Default")
      (node (ref "U4") (pin "12") (pinfunction "~{CS}_12") (pintype "bidirectional"))
    )
  )
)
